# Microcontrolador.net
KiCad netlist of a schematic drawn in Altium Designer
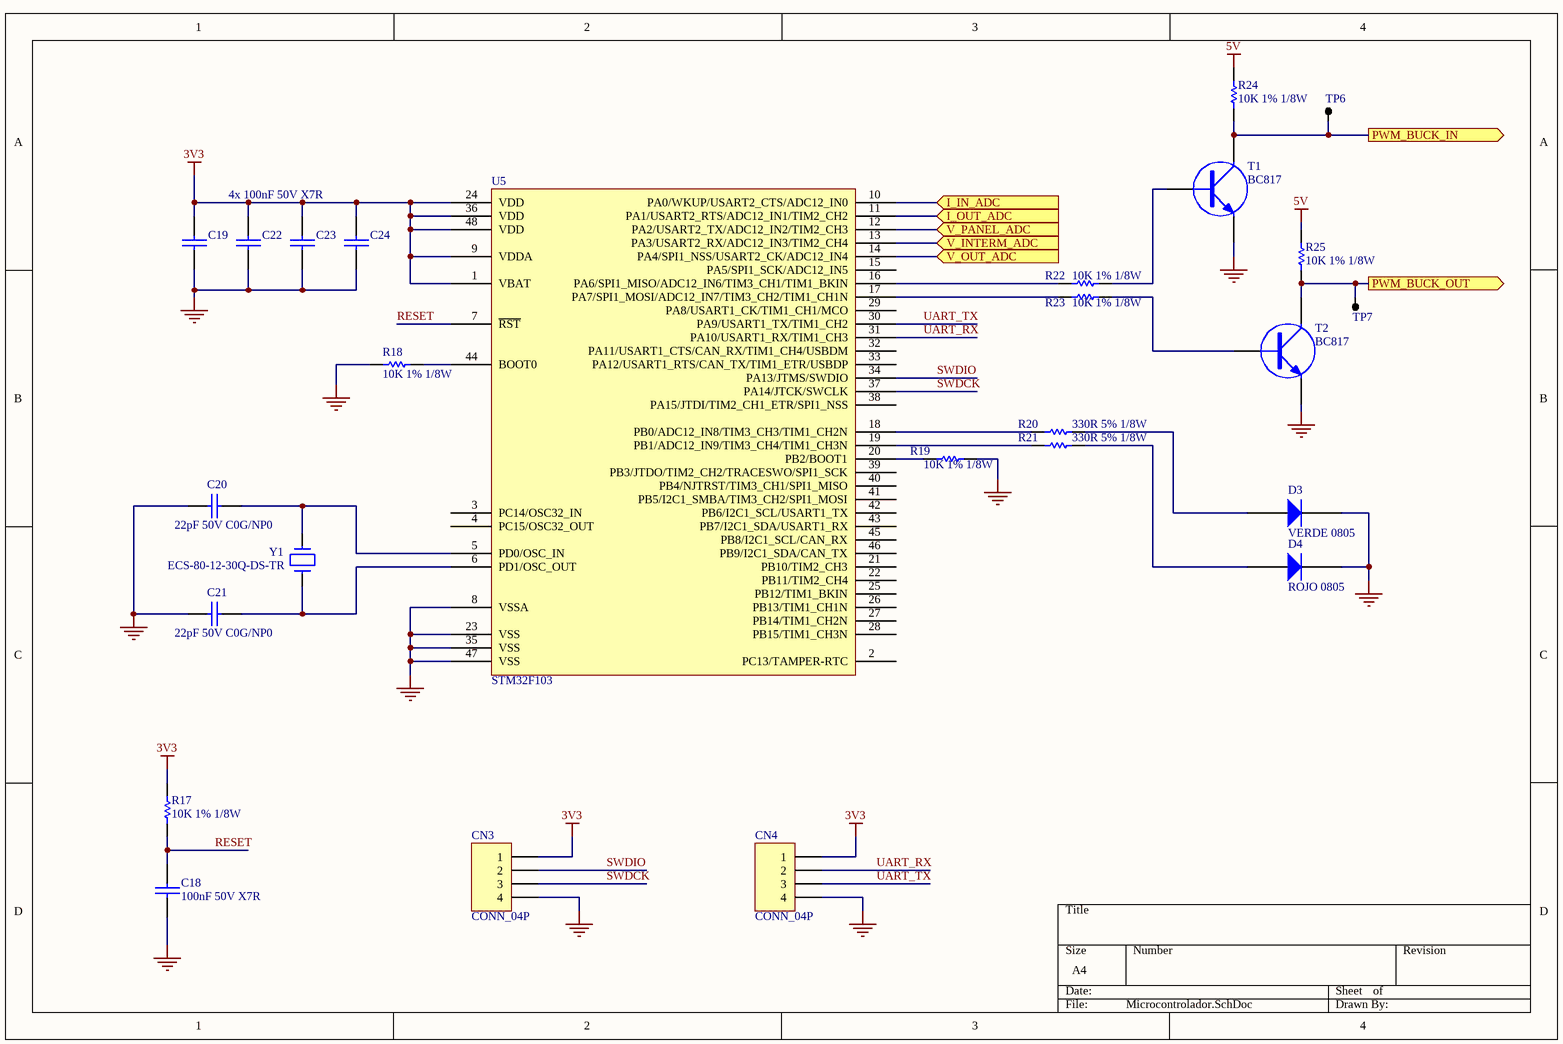
[diagram p0: Microcontrolador.SchDoc]

(export (version "E")
  (design (tool "Eeschema 10.0.6"))
  (components
    (comp (ref "C18")
      (value "100nF 50V X7R")
      (footprint "0805")
      (libsource (lib "Libreria_Casera") (part "CAP"))
    )
    (comp (ref "C19")
      (value "100nF 50V X7R")
      (footprint "0805")
      (libsource (lib "Libreria_Casera") (part "CAP"))
    )
    (comp (ref "C20")
      (value "22pF 50V C0G/NP0")
      (footprint "0805")
      (libsource (lib "Libreria_Casera") (part "CAP"))
    )
    (comp (ref "C21")
      (value "22pF 50V C0G/NP0")
      (footprint "0805")
      (libsource (lib "Libreria_Casera") (part "CAP"))
    )
    (comp (ref "C22")
      (value "100nF 50V X7R")
      (footprint "0805")
      (libsource (lib "Libreria_Casera") (part "CAP"))
    )
    (comp (ref "C23")
      (value "100nF 50V X7R")
      (footprint "0805")
      (libsource (lib "Libreria_Casera") (part "CAP"))
    )
    (comp (ref "C24")
      (value "100nF 50V X7R")
      (footprint "0805")
      (libsource (lib "Libreria_Casera") (part "CAP"))
    )
    (comp (ref "CN3")
      (value "CONN_04P")
      (footprint "MOLEX4 - 0.1\"")
      (description "Connector Generic 4 Vias")
      (libsource (lib "MPPTLib") (part "CONN_04P"))
    )
    (comp (ref "CN4")
      (value "CONN_04P")
      (footprint "MOLEX4 - 0.1\"")
      (description "Connector Generic 4 Vias")
      (libsource (lib "MPPTLib") (part "CONN_04P"))
    )
    (comp (ref "D3")
      (value "VERDE 0805")
      (footprint "LED0805")
      (libsource (lib "Libreria_Casera") (part "Led"))
    )
    (comp (ref "D4")
      (value "ROJO 0805")
      (footprint "LED0805")
      (libsource (lib "Libreria_Casera") (part "Led"))
    )
    (comp (ref "R17")
      (value "10K 1% 1/8W")
      (footprint "0805")
      (libsource (lib "Libreria_Casera") (part "RES"))
    )
    (comp (ref "R18")
      (value "10K 1% 1/8W")
      (footprint "0805")
      (libsource (lib "Libreria_Casera") (part "RES"))
    )
    (comp (ref "R19")
      (value "10K 1% 1/8W")
      (footprint "0805")
      (libsource (lib "Libreria_Casera") (part "RES"))
    )
    (comp (ref "R20")
      (value "330R 5% 1/8W")
      (footprint "0805")
      (libsource (lib "Libreria_Casera") (part "RES"))
    )
    (comp (ref "R21")
      (value "330R 5% 1/8W")
      (footprint "0805")
      (libsource (lib "Libreria_Casera") (part "RES"))
    )
    (comp (ref "R22")
      (value "10K 1% 1/8W")
      (footprint "0805")
      (libsource (lib "Libreria_Casera") (part "RES"))
    )
    (comp (ref "R23")
      (value "10K 1% 1/8W")
      (footprint "0805")
      (libsource (lib "Libreria_Casera") (part "RES"))
    )
    (comp (ref "R24")
      (value "10K 1% 1/8W")
      (footprint "0805")
      (libsource (lib "Libreria_Casera") (part "RES"))
    )
    (comp (ref "R25")
      (value "10K 1% 1/8W")
      (footprint "0805")
      (libsource (lib "Libreria_Casera") (part "RES"))
    )
    (comp (ref "T1")
      (value "BC817")
      (footprint "SOT23")
      (libsource (lib "Libreria_Casera") (part "TRANSISTOR NPN"))
    )
    (comp (ref "T2")
      (value "BC817")
      (footprint "SOT23")
      (libsource (lib "Libreria_Casera") (part "TRANSISTOR NPN"))
    )
    (comp (ref "TP6") (value "TP") (footprint "TP_COMPACT") (libsource (lib "Libreria_Casera") (part "TP")))
    (comp (ref "TP7") (value "TP") (footprint "TP_COMPACT") (libsource (lib "Libreria_Casera") (part "TP")))
    (comp (ref "U5")
      (value "STM32F103")
      (footprint "LQFP48 - 7x7")
      (libsource (lib "MPPTLib") (part "STM32F103"))
    )
    (comp (ref "Y1")
      (value "ECS-80-12-30Q-DS-TR")
      (footprint "ECS 2-SMD")
      (libsource (lib "Libreria_Casera") (part "CRISTAL"))
    )
  )
  (nets
    (net (code "1") (name "/I_IN_ADC") (class "Default")
      (node (ref "U5") (pin "10") (pinfunction "PA0/WKUP/USART2_CTS/ADC12_IN0_10") (pintype "passive"))
    )
    (net (code "2") (name "/I_OUT_ADC") (class "Default")
      (node (ref "U5") (pin "11") (pinfunction "PA1/USART2_RTS/ADC12_IN1/TIM2_CH2_11") (pintype "passive"))
    )
    (net (code "3") (name "/PWM_BUCK_IN") (class "Default")
      (node (ref "R24") (pin "1") (pinfunction "1_1") (pintype "passive"))
      (node (ref "T1") (pin "2") (pinfunction "C_2") (pintype "passive"))
      (node (ref "TP6") (pin "1") (pinfunction "1_1") (pintype "passive"))
    )
    (net (code "4") (name "/PWM_BUCK_OUT") (class "Default")
      (node (ref "R25") (pin "1") (pinfunction "1_1") (pintype "passive"))
      (node (ref "T2") (pin "2") (pinfunction "C_2") (pintype "passive"))
      (node (ref "TP7") (pin "1") (pinfunction "1_1") (pintype "passive"))
    )
    (net (code "5") (name "/RESET") (class "Default")
      (node (ref "C18") (pin "2") (pinfunction "2_2") (pintype "passive"))
      (node (ref "R17") (pin "1") (pinfunction "1_1") (pintype "passive"))
      (node (ref "U5") (pin "7") (pinfunction "~{RST}_7") (pintype "passive"))
    )
    (net (code "6") (name "/SWDCK") (class "Default")
      (node (ref "CN3") (pin "3") (pinfunction "3_3") (pintype "passive"))
      (node (ref "U5") (pin "37") (pinfunction "PA14/JTCK/SWCLK_37") (pintype "passive"))
    )
    (net (code "7") (name "/SWDIO") (class "Default")
      (node (ref "CN3") (pin "2") (pinfunction "2_2") (pintype "passive"))
      (node (ref "U5") (pin "34") (pinfunction "PA13/JTMS/SWDIO_34") (pintype "passive"))
    )
    (net (code "8") (name "/UART_RX") (class "Default")
      (node (ref "CN4") (pin "2") (pinfunction "2_2") (pintype "passive"))
      (node (ref "U5") (pin "31") (pinfunction "PA10/USART1_RX/TIM1_CH3_31") (pintype "passive"))
    )
    (net (code "9") (name "/UART_TX") (class "Default")
      (node (ref "CN4") (pin "3") (pinfunction "3_3") (pintype "passive"))
      (node (ref "U5") (pin "30") (pinfunction "PA9/USART1_TX/TIM1_CH2_30") (pintype "passive"))
    )
    (net (code "10") (name "/V_INTERM_ADC") (class "Default")
      (node (ref "U5") (pin "13") (pinfunction "PA3/USART2_RX/ADC12_IN3/TIM2_CH4_13") (pintype "passive"))
    )
    (net (code "11") (name "/V_OUT_ADC") (class "Default")
      (node (ref "U5") (pin "14") (pinfunction "PA4/SPI1_NSS/USART2_CK/ADC12_IN4_14") (pintype "passive"))
    )
    (net (code "12") (name "/V_PANEL_ADC") (class "Default")
      (node (ref "U5") (pin "12") (pinfunction "PA2/USART2_TX/ADC12_IN2/TIM2_CH3_12") (pintype "passive"))
    )
    (net (code "13") (name "3V3") (class "Default")
      (node (ref "C19") (pin "2") (pinfunction "2_2") (pintype "passive"))
      (node (ref "C22") (pin "2") (pinfunction "2_2") (pintype "passive"))
      (node (ref "C23") (pin "2") (pinfunction "2_2") (pintype "passive"))
      (node (ref "C24") (pin "2") (pinfunction "2_2") (pintype "passive"))
      (node (ref "CN3") (pin "1") (pinfunction "1_1") (pintype "passive"))
      (node (ref "CN4") (pin "1") (pinfunction "1_1") (pintype "passive"))
      (node (ref "R17") (pin "2") (pinfunction "2_2") (pintype "passive"))
      (node (ref "U5") (pin "1") (pinfunction "VBAT_1") (pintype "passive"))
      (node (ref "U5") (pin "24") (pinfunction "VDD_24") (pintype "passive"))
      (node (ref "U5") (pin "36") (pinfunction "VDD_36") (pintype "passive"))
      (node (ref "U5") (pin "48") (pinfunction "VDD_48") (pintype "passive"))
      (node (ref "U5") (pin "9") (pinfunction "VDDA_9") (pintype "passive"))
    )
    (net (code "14") (name "5V") (class "Default")
      (node (ref "R24") (pin "2") (pinfunction "2_2") (pintype "passive"))
      (node (ref "R25") (pin "2") (pinfunction "2_2") (pintype "passive"))
    )
    (net (code "15") (name "GND") (class "Default")
      (node (ref "C18") (pin "1") (pinfunction "1_1") (pintype "passive"))
      (node (ref "C19") (pin "1") (pinfunction "1_1") (pintype "passive"))
      (node (ref "C20") (pin "2") (pinfunction "2_2") (pintype "passive"))
      (node (ref "C21") (pin "2") (pinfunction "2_2") (pintype "passive"))
      (node (ref "C22") (pin "1") (pinfunction "1_1") (pintype "passive"))
      (node (ref "C23") (pin "1") (pinfunction "1_1") (pintype "passive"))
      (node (ref "C24") (pin "1") (pinfunction "1_1") (pintype "passive"))
      (node (ref "CN3") (pin "4") (pinfunction "4_4") (pintype "passive"))
      (node (ref "CN4") (pin "4") (pinfunction "4_4") (pintype "passive"))
      (node (ref "D3") (pin "K") (pinfunction "37_K") (pintype "passive"))
      (node (ref "D4") (pin "K") (pinfunction "37_K") (pintype "passive"))
      (node (ref "R18") (pin "1") (pinfunction "1_1") (pintype "passive"))
      (node (ref "R19") (pin "2") (pinfunction "2_2") (pintype "passive"))
      (node (ref "T1") (pin "3") (pinfunction "E_3") (pintype "passive"))
      (node (ref "T2") (pin "3") (pinfunction "E_3") (pintype "passive"))
      (node (ref "U5") (pin "23") (pinfunction "VSS_23") (pintype "passive"))
      (node (ref "U5") (pin "35") (pinfunction "VSS_35") (pintype "passive"))
      (node (ref "U5") (pin "47") (pinfunction "VSS_47") (pintype "passive"))
      (node (ref "U5") (pin "8") (pinfunction "VSSA_8") (pintype "passive"))
    )
    (net (code "16") (name "Net-(D3-36)") (class "Default")
      (node (ref "D3") (pin "A") (pinfunction "36_A") (pintype "passive"))
      (node (ref "R20") (pin "2") (pinfunction "2_2") (pintype "passive"))
    )
    (net (code "17") (name "Net-(D4-36)") (class "Default")
      (node (ref "D4") (pin "A") (pinfunction "36_A") (pintype "passive"))
      (node (ref "R21") (pin "2") (pinfunction "2_2") (pintype "passive"))
    )
    (net (code "18") (name "Net-(T1-B)") (class "Default")
      (node (ref "R22") (pin "2") (pinfunction "2_2") (pintype "passive"))
      (node (ref "T1") (pin "1") (pinfunction "B_1") (pintype "passive"))
    )
    (net (code "19") (name "Net-(T2-B)") (class "Default")
      (node (ref "R23") (pin "2") (pinfunction "2_2") (pintype "passive"))
      (node (ref "T2") (pin "1") (pinfunction "B_1") (pintype "passive"))
    )
    (net (code "20") (name "Net-(U5-BOOT0)") (class "Default")
      (node (ref "R18") (pin "2") (pinfunction "2_2") (pintype "passive"))
      (node (ref "U5") (pin "44") (pinfunction "BOOT0_44") (pintype "passive"))
    )
    (net (code "21") (name "Net-(U5-PA6{slash}SPI1_MISO{slash}ADC12_IN6{slash}TIM3_CH1{slash}TIM1_BKIN)") (class "Default")
      (node (ref "R22") (pin "1") (pinfunction "1_1") (pintype "passive"))
      (node (ref "U5") (pin "16") (pinfunction "PA6/SPI1_MISO/ADC12_IN6/TIM3_CH1/TIM1_BKIN_16") (pintype "passive"))
    )
    (net (code "22") (name "Net-(U5-PA7{slash}SPI1_MOSI{slash}ADC12_IN7{slash}TIM3_CH2{slash}TIM1_CH1N)") (class "Default")
      (node (ref "R23") (pin "1") (pinfunction "1_1") (pintype "passive"))
      (node (ref "U5") (pin "17") (pinfunction "PA7/SPI1_MOSI/ADC12_IN7/TIM3_CH2/TIM1_CH1N_17") (pintype "passive"))
    )
    (net (code "23") (name "Net-(U5-PB0{slash}ADC12_IN8{slash}TIM3_CH3{slash}TIM1_CH2N)") (class "Default")
      (node (ref "R20") (pin "1") (pinfunction "1_1") (pintype "passive"))
      (node (ref "U5") (pin "18") (pinfunction "PB0/ADC12_IN8/TIM3_CH3/TIM1_CH2N_18") (pintype "passive"))
    )
    (net (code "24") (name "Net-(U5-PB1{slash}ADC12_IN9{slash}TIM3_CH4{slash}TIM1_CH3N)") (class "Default")
      (node (ref "R21") (pin "1") (pinfunction "1_1") (pintype "passive"))
      (node (ref "U5") (pin "19") (pinfunction "PB1/ADC12_IN9/TIM3_CH4/TIM1_CH3N_19") (pintype "passive"))
    )
    (net (code "25") (name "Net-(U5-PB2{slash}BOOT1)") (class "Default")
      (node (ref "R19") (pin "1") (pinfunction "1_1") (pintype "passive"))
      (node (ref "U5") (pin "20") (pinfunction "PB2/BOOT1_20") (pintype "passive"))
    )
    (net (code "26") (name "Net-(U5-PD0{slash}OSC_IN)") (class "Default")
      (node (ref "C20") (pin "1") (pinfunction "1_1") (pintype "passive"))
      (node (ref "U5") (pin "5") (pinfunction "PD0/OSC_IN_5") (pintype "passive"))
      (node (ref "Y1") (pin "2") (pinfunction "10_2") (pintype "passive"))
    )
    (net (code "27") (name "Net-(U5-PD1{slash}OSC_OUT)") (class "Default")
      (node (ref "C21") (pin "1") (pinfunction "1_1") (pintype "passive"))
      (node (ref "U5") (pin "6") (pinfunction "PD1/OSC_OUT_6") (pintype "passive"))
      (node (ref "Y1") (pin "1") (pinfunction "1_1") (pintype "passive"))
    )
    (net (code "28") (name "unconnected-(U5-PA5{slash}SPI1_SCK{slash}ADC12_IN5-Pad15)") (class "Default")
      (node (ref "U5") (pin "15") (pinfunction "PA5/SPI1_SCK/ADC12_IN5_15") (pintype "passive"))
    )
    (net (code "29") (name "unconnected-(U5-PA8{slash}USART1_CK{slash}TIM1_CH1{slash}MCO-Pad29)") (class "Default")
      (node (ref "U5") (pin "29") (pinfunction "PA8/USART1_CK/TIM1_CH1/MCO_29") (pintype "passive"))
    )
    (net (code "30") (name "unconnected-(U5-PA11{slash}USART1_CTS{slash}CAN_RX{slash}TIM1_CH4{slash}USBDM-Pad32)") (class "Default")
      (node (ref "U5") (pin "32") (pinfunction "PA11/USART1_CTS/CAN_RX/TIM1_CH4/USBDM_32") (pintype "passive"))
    )
    (net (code "31") (name "unconnected-(U5-PA12{slash}USART1_RTS{slash}CAN_TX{slash}TIM1_ETR{slash}USBDP-Pad33)") (class "Default")
      (node (ref "U5") (pin "33") (pinfunction "PA12/USART1_RTS/CAN_TX/TIM1_ETR/USBDP_33") (pintype "passive"))
    )
    (net (code "32") (name "unconnected-(U5-PA15{slash}JTDI{slash}TIM2_CH1_ETR{slash}SPI1_NSS-Pad38)") (class "Default")
      (node (ref "U5") (pin "38") (pinfunction "PA15/JTDI/TIM2_CH1_ETR/SPI1_NSS_38") (pintype "passive"))
    )
    (net (code "33") (name "unconnected-(U5-PB3{slash}JTDO{slash}TIM2_CH2{slash}TRACESWO{slash}SPI1_SCK-Pad39)") (class "Default")
      (node (ref "U5") (pin "39") (pinfunction "PB3/JTDO/TIM2_CH2/TRACESWO/SPI1_SCK_39") (pintype "passive"))
    )
    (net (code "34") (name "unconnected-(U5-PB4{slash}NJTRST{slash}TIM3_CH1{slash}SPI1_MISO-Pad40)") (class "Default")
      (node (ref "U5") (pin "40") (pinfunction "PB4/NJTRST/TIM3_CH1/SPI1_MISO_40") (pintype "passive"))
    )
    (net (code "35") (name "unconnected-(U5-PB5{slash}I2C1_SMBA{slash}TIM3_CH2{slash}SPI1_MOSI-Pad41)") (class "Default")
      (node (ref "U5") (pin "41") (pinfunction "PB5/I2C1_SMBA/TIM3_CH2/SPI1_MOSI_41") (pintype "passive"))
    )
    (net (code "36") (name "unconnected-(U5-PB6{slash}I2C1_SCL{slash}USART1_TX-Pad42)") (class "Default")
      (node (ref "U5") (pin "42") (pinfunction "PB6/I2C1_SCL/USART1_TX_42") (pintype "passive"))
    )
    (net (code "37") (name "unconnected-(U5-PB7{slash}I2C1_SDA{slash}USART1_RX-Pad43)") (class "Default")
      (node (ref "U5") (pin "43") (pinfunction "PB7/I2C1_SDA/USART1_RX_43") (pintype "passive"))
    )
    (net (code "38") (name "unconnected-(U5-PB8{slash}I2C1_SCL{slash}CAN_RX-Pad45)") (class "Default")
      (node (ref "U5") (pin "45") (pinfunction "PB8/I2C1_SCL/CAN_RX_45") (pintype "passive"))
    )
    (net (code "39") (name "unconnected-(U5-PB9{slash}I2C1_SDA{slash}CAN_TX-Pad46)") (class "Default")
      (node (ref "U5") (pin "46") (pinfunction "PB9/I2C1_SDA/CAN_TX_46") (pintype "passive"))
    )
    (net (code "40") (name "unconnected-(U5-PB10{slash}TIM2_CH3-Pad21)") (class "Default")
      (node (ref "U5") (pin "21") (pinfunction "PB10/TIM2_CH3_21") (pintype "passive"))
    )
    (net (code "41") (name "unconnected-(U5-PB11{slash}TIM2_CH4-Pad22)") (class "Default")
      (node (ref "U5") (pin "22") (pinfunction "PB11/TIM2_CH4_22") (pintype "passive"))
    )
    (net (code "42") (name "unconnected-(U5-PB12{slash}TIM1_BKIN-Pad25)") (class "Default")
      (node (ref "U5") (pin "25") (pinfunction "PB12/TIM1_BKIN_25") (pintype "passive"))
    )
    (net (code "43") (name "unconnected-(U5-PB13{slash}TIM1_CH1N-Pad26)") (class "Default")
      (node (ref "U5") (pin "26") (pinfunction "PB13/TIM1_CH1N_26") (pintype "passive"))
    )
    (net (code "44") (name "unconnected-(U5-PB14{slash}TIM1_CH2N-Pad27)") (class "Default")
      (node (ref "U5") (pin "27") (pinfunction "PB14/TIM1_CH2N_27") (pintype "passive"))
    )
    (net (code "45") (name "unconnected-(U5-PB15{slash}TIM1_CH3N-Pad28)") (class "Default")
      (node (ref "U5") (pin "28") (pinfunction "PB15/TIM1_CH3N_28") (pintype "passive"))
    )
    (net (code "46") (name "unconnected-(U5-PC13{slash}TAMPER-RTC-Pad2)") (class "Default")
      (node (ref "U5") (pin "2") (pinfunction "PC13/TAMPER-RTC_2") (pintype "passive"))
    )
    (net (code "47") (name "unconnected-(U5-PC14{slash}OSC32_IN-Pad3)") (class "Default")
      (node (ref "U5") (pin "3") (pinfunction "PC14/OSC32_IN_3") (pintype "passive"))
    )
    (net (code "48") (name "unconnected-(U5-PC15{slash}OSC32_OUT-Pad4)") (class "Default")
      (node (ref "U5") (pin "4") (pinfunction "PC15/OSC32_OUT_4") (pintype "passive"))
    )
  )
)
